# control.net
KiCad netlist of a schematic drawn in Altium Designer
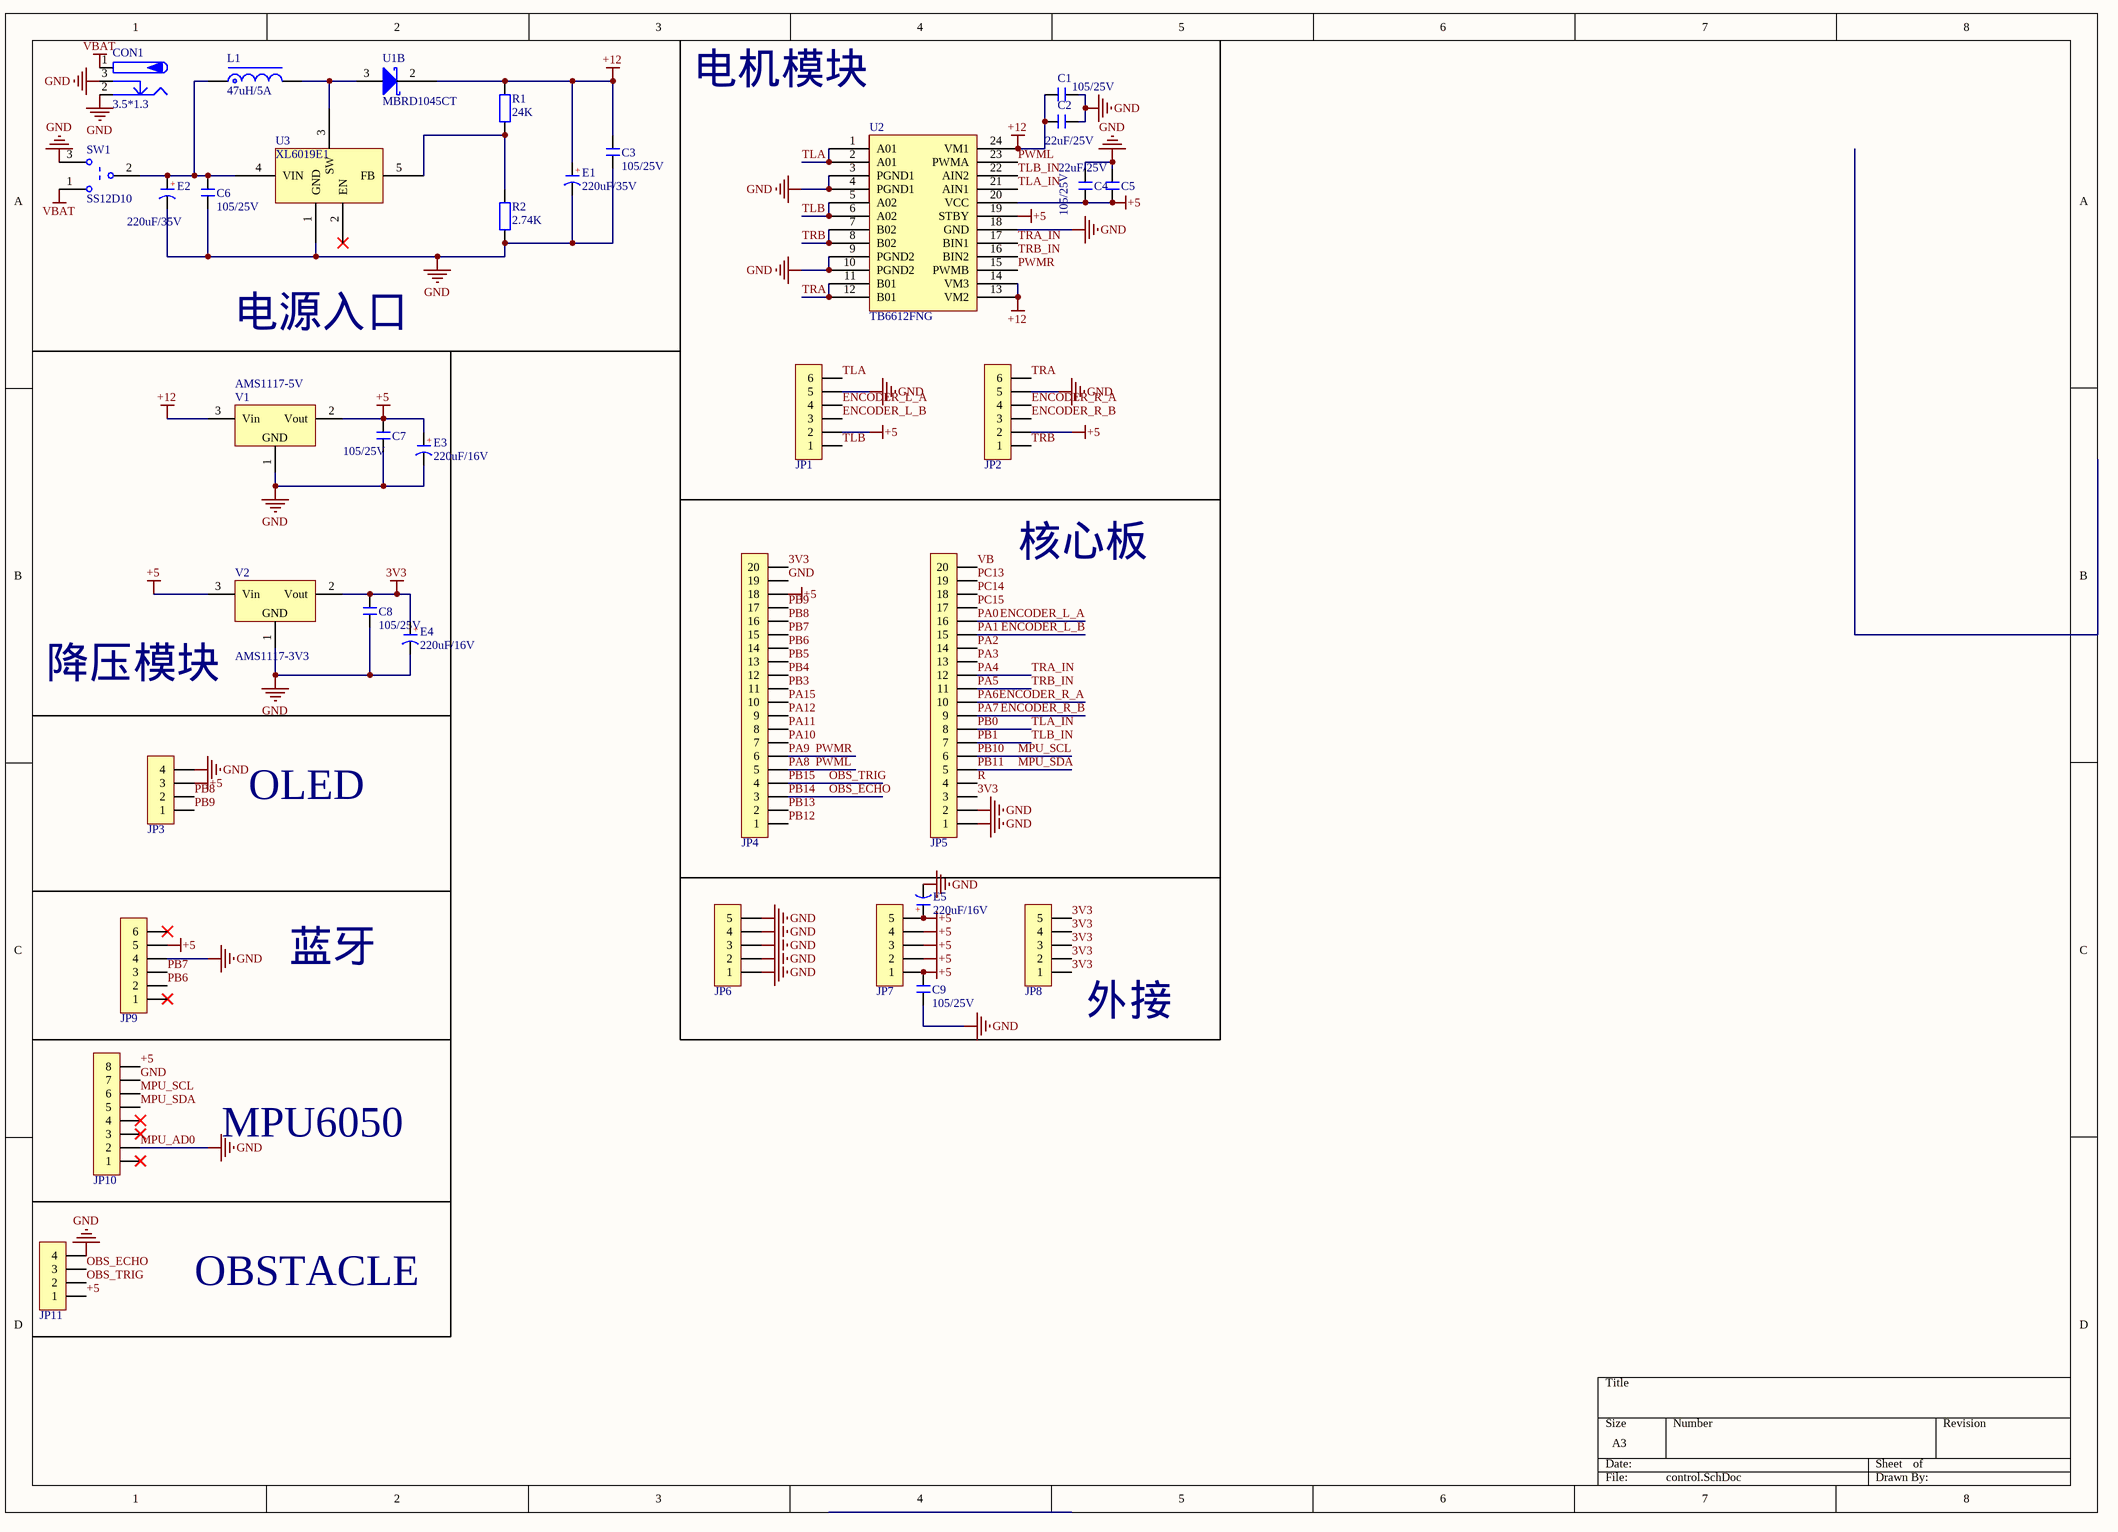
[diagram p0: control.SchDoc]

(export (version "E")
  (design (tool "Eeschema 10.0.6"))
  (components
    (comp (ref "C1")
      (value "105/25V")
      (footprint "C 0603_M")
      (description "贴片电容")
      (libsource (lib "0.1 - 电阻-电容-电感") (part "C"))
    )
    (comp (ref "C2")
      (value "22uF/25V")
      (footprint "C 0805_M")
      (description "贴片电容")
      (libsource (lib "0.1 - 电阻-电容-电感") (part "C"))
    )
    (comp (ref "C3")
      (value "105/25V")
      (footprint "C 0603_M")
      (description "贴片电容")
      (libsource (lib "0.1 - 电阻-电容-电感") (part "C"))
    )
    (comp (ref "C4")
      (value "105/25V")
      (footprint "C 0603_M")
      (description "贴片电容")
      (libsource (lib "0.1 - 电阻-电容-电感") (part "C"))
    )
    (comp (ref "C5")
      (value "22uF/25V")
      (footprint "C 0805_M")
      (description "贴片电容")
      (libsource (lib "0.1 - 电阻-电容-电感") (part "C"))
    )
    (comp (ref "C6")
      (value "105/25V")
      (footprint "C 0603_M")
      (description "贴片电容")
      (libsource (lib "0.1 - 电阻-电容-电感") (part "C"))
    )
    (comp (ref "C7")
      (value "105/25V")
      (footprint "C 0603_M")
      (description "贴片电容")
      (libsource (lib "0.1 - 电阻-电容-电感") (part "C"))
    )
    (comp (ref "C8")
      (value "105/25V")
      (footprint "C 0603_M")
      (description "贴片电容")
      (libsource (lib "0.1 - 电阻-电容-电感") (part "C"))
    )
    (comp (ref "C9")
      (value "105/25V")
      (footprint "C 0603_M")
      (description "贴片电容")
      (libsource (lib "0.1 - 电阻-电容-电感") (part "C"))
    )
    (comp (ref "CON1")
      (value "3.5*1.3")
      (footprint "DC-005")
      (description "低压电源接口")
      (fields (field (name "版权归属") "封装库来自淘宝 ID：黄晶宝石"))
      (libsource (lib "0.8 - 以太网-音频-USB插座") (part "P-DC"))
    )
    (comp (ref "E1")
      (value "220uF/35V")
      (footprint "CM E(8*10.2)")
      (description "贴片电解电容")
      (fields (field (name "版权归属") "封装库来自淘宝 ID：黄晶宝石"))
      (libsource (lib "0.1 - 电阻-电容-电感") (part "CE_SMD"))
    )
    (comp (ref "E2")
      (value "220uF/35V")
      (footprint "CM E(8*10.2)")
      (description "贴片电解电容")
      (fields (field (name "版权归属") "封装库来自淘宝 ID：黄晶宝石"))
      (libsource (lib "0.1 - 电阻-电容-电感") (part "CE_SMD"))
    )
    (comp (ref "E3")
      (value "220uF/16V")
      (footprint "CD D(7343)")
      (description "贴片钽电容")
      (libsource (lib "0.1 - 电阻-电容-电感") (part "CT"))
    )
    (comp (ref "E4")
      (value "220uF/16V")
      (footprint "CD D(7343)")
      (description "贴片钽电容")
      (libsource (lib "0.1 - 电阻-电容-电感") (part "CT"))
    )
    (comp (ref "E5")
      (value "220uF/16V")
      (footprint "CD D(7343)")
      (description "贴片钽电容")
      (libsource (lib "0.1 - 电阻-电容-电感") (part "CT"))
    )
    (comp (ref "JP1")
      (value "HDR-1X6")
      (footprint "XH2.54-LI-6P")
      (description "6P接插件")
      (fields (field (name "版权归属") "封装库来自淘宝 ID：黄晶宝石"))
      (libsource (lib "5.4 - 接插件-脚距2.54 (100mil) ") (part "Header 6"))
    )
    (comp (ref "JP2")
      (value "HDR-1X6")
      (footprint "XH2.54-LI-6P")
      (description "6P接插件")
      (fields (field (name "版权归属") "封装库来自淘宝 ID：黄晶宝石"))
      (libsource (lib "5.4 - 接插件-脚距2.54 (100mil) ") (part "Header 6"))
    )
    (comp (ref "JP3")
      (value "HDR-1X4")
      (footprint "HDR2.54-M-LI-4P")
      (description "4P接插件")
      (fields (field (name "版权归属") "封装库来自淘宝 ID：黄晶宝石"))
      (libsource (lib "5.4 - 接插件-脚距2.54 (100mil) ") (part "Header 4"))
    )
    (comp (ref "JP4")
      (value "HDR-1X20")
      (footprint "HDR2.54-M-LI-20P")
      (description "20P接插件")
      (fields (field (name "版权归属") "封装库来自淘宝 ID：黄晶宝石"))
      (libsource (lib "5.4 - 接插件-脚距2.54 (100mil) ") (part "Header 20"))
    )
    (comp (ref "JP5")
      (value "HDR-1X20")
      (footprint "HDR2.54-M-LI-20P")
      (description "20P接插件")
      (fields (field (name "版权归属") "封装库来自淘宝 ID：黄晶宝石"))
      (libsource (lib "5.4 - 接插件-脚距2.54 (100mil) ") (part "Header 20"))
    )
    (comp (ref "JP6")
      (value "HDR-1X5")
      (footprint "HDR2.54-LI-5P")
      (description "5P接插件")
      (fields (field (name "版权归属") "封装库来自淘宝 ID：黄晶宝石"))
      (libsource (lib "5.4 - 接插件-脚距2.54 (100mil) ") (part "Header 5"))
    )
    (comp (ref "JP7")
      (value "HDR-1X5")
      (footprint "HDR2.54-LI-5P")
      (description "5P接插件")
      (fields (field (name "版权归属") "封装库来自淘宝 ID：黄晶宝石"))
      (libsource (lib "5.4 - 接插件-脚距2.54 (100mil) ") (part "Header 5"))
    )
    (comp (ref "JP8")
      (value "HDR-1X5")
      (footprint "HDR2.54-LI-5P")
      (description "5P接插件")
      (fields (field (name "版权归属") "封装库来自淘宝 ID：黄晶宝石"))
      (libsource (lib "5.4 - 接插件-脚距2.54 (100mil) ") (part "Header 5"))
    )
    (comp (ref "JP9")
      (value "HDR-1X6")
      (footprint "HDR2.54-M-LI-6P")
      (description "6P接插件")
      (fields (field (name "版权归属") "封装库来自淘宝 ID：黄晶宝石"))
      (libsource (lib "5.4 - 接插件-脚距2.54 (100mil) ") (part "Header 6"))
    )
    (comp (ref "JP10")
      (value "HDR-1X8")
      (footprint "HDR2.54-M-LI-8P")
      (description "8P接插件")
      (fields (field (name "版权归属") "封装库来自淘宝 ID：黄晶宝石"))
      (libsource (lib "5.4 - 接插件-脚距2.54 (100mil) ") (part "Header 8"))
    )
    (comp (ref "JP11")
      (value "HDR-1X4")
      (footprint "HDR2.54-M-LI-4P")
      (description "4P接插件")
      (fields (field (name "版权归属") "封装库来自淘宝 ID：黄晶宝石"))
      (libsource (lib "5.4 - 接插件-脚距2.54 (100mil) ") (part "Header 4"))
    )
    (comp (ref "L1")
      (value "47uH/5A")
      (footprint "LMR135")
      (description "功率磁环电感")
      (libsource (lib "0.1 - 电阻-电容-电感") (part "L-MR"))
    )
    (comp (ref "R1")
      (value "24K")
      (footprint "R 0603_M")
      (description "贴片电阻")
      (fields (field (name "版权归属") "来自淘宝 ID：黄晶宝石"))
      (libsource (lib "0.1 - 电阻-电容-电感") (part "R"))
    )
    (comp (ref "R2")
      (value "2.74K")
      (footprint "R 0603_M")
      (description "贴片电阻")
      (fields (field (name "版权归属") "来自淘宝 ID：黄晶宝石"))
      (libsource (lib "0.1 - 电阻-电容-电感") (part "R"))
    )
    (comp (ref "SW1") (value "SS12D10") (footprint "SS12D10") (libsource (lib "LJY_LIB") (part "SS12D10")))
    (comp (ref "U1")
      (value "MBRD1045CT")
      (footprint "TO-252-3_L6.5-W5.5-P4.6-LS9.5-BL")
      (libsource (lib "LJY_LIB") (part "MBRD1045CT"))
    )
    (comp (ref "U2")
      (value "TB6612FNG")
      (footprint "TSOP65P760X160-24N")
      (libsource (lib "LJY_LIB") (part "TB6612FNG"))
    )
    (comp (ref "U3") (value "XL6019E1") (footprint "TO-263-5") (libsource (lib "LJY_LIB") (part "XL6019E1")))
    (comp (ref "V1")
      (value "AMS1117-5V")
      (footprint "SOT223_L")
      (description "三端稳压芯片")
      (libsource (lib "1.1 - 电源类芯片") (part "AMS1117"))
    )
    (comp (ref "V2")
      (value "AMS1117-3V3")
      (footprint "SOT223_L")
      (description "三端稳压芯片")
      (libsource (lib "1.1 - 电源类芯片") (part "AMS1117"))
    )
  )
  (nets
    (net (code "1") (name "+5") (class "Default")
      (node (ref "C4") (pin "2") (pinfunction "2_2") (pintype "passive"))
      (node (ref "C5") (pin "2") (pinfunction "2_2") (pintype "passive"))
      (node (ref "C7") (pin "2") (pinfunction "2_2") (pintype "passive"))
      (node (ref "C9") (pin "2") (pinfunction "2_2") (pintype "passive"))
      (node (ref "E3") (pin "1") (pinfunction "A_1") (pintype "passive"))
      (node (ref "E5") (pin "1") (pinfunction "A_1") (pintype "passive"))
      (node (ref "JP1") (pin "2") (pinfunction "2_2") (pintype "passive"))
      (node (ref "JP10") (pin "8") (pinfunction "8_8") (pintype "passive"))
      (node (ref "JP11") (pin "1") (pinfunction "1_1") (pintype "passive"))
      (node (ref "JP2") (pin "2") (pinfunction "2_2") (pintype "passive"))
      (node (ref "JP3") (pin "3") (pinfunction "3_3") (pintype "passive"))
      (node (ref "JP4") (pin "18") (pinfunction "18_18") (pintype "passive"))
      (node (ref "JP7") (pin "1") (pinfunction "1_1") (pintype "passive"))
      (node (ref "JP7") (pin "2") (pinfunction "2_2") (pintype "passive"))
      (node (ref "JP7") (pin "3") (pinfunction "3_3") (pintype "passive"))
      (node (ref "JP7") (pin "4") (pinfunction "4_4") (pintype "passive"))
      (node (ref "JP7") (pin "5") (pinfunction "5_5") (pintype "passive"))
      (node (ref "JP9") (pin "5") (pinfunction "5_5") (pintype "passive"))
      (node (ref "U2") (pin "19") (pinfunction "STBY_19") (pintype "passive"))
      (node (ref "U2") (pin "20") (pinfunction "VCC_20") (pintype "passive"))
      (node (ref "V1") (pin "2") (pinfunction "Vout_2") (pintype "passive"))
      (node (ref "V2") (pin "3") (pinfunction "Vin_3") (pintype "passive"))
    )
    (net (code "2") (name "+12") (class "Default")
      (node (ref "C1") (pin "2") (pinfunction "2_2") (pintype "passive"))
      (node (ref "C2") (pin "2") (pinfunction "2_2") (pintype "passive"))
      (node (ref "C3") (pin "2") (pinfunction "2_2") (pintype "passive"))
      (node (ref "E1") (pin "1") (pinfunction "A_1") (pintype "passive"))
      (node (ref "R1") (pin "2") (pinfunction "2_2") (pintype "passive"))
      (node (ref "U1") (pin "2") (pinfunction "3_2") (pintype "passive"))
      (node (ref "U2") (pin "13") (pinfunction "VM2_13") (pintype "passive"))
      (node (ref "U2") (pin "14") (pinfunction "VM3_14") (pintype "passive"))
      (node (ref "U2") (pin "24") (pinfunction "VM1_24") (pintype "passive"))
      (node (ref "V1") (pin "3") (pinfunction "Vin_3") (pintype "passive"))
    )
    (net (code "3") (name "/ENCODER_L_A") (class "Default")
      (node (ref "JP1") (pin "4") (pinfunction "4_4") (pintype "passive"))
      (node (ref "JP5") (pin "16") (pinfunction "16_16") (pintype "passive"))
    )
    (net (code "4") (name "/ENCODER_L_B") (class "Default")
      (node (ref "JP1") (pin "3") (pinfunction "3_3") (pintype "passive"))
      (node (ref "JP5") (pin "15") (pinfunction "15_15") (pintype "passive"))
    )
    (net (code "5") (name "/ENCODER_R_A") (class "Default")
      (node (ref "JP2") (pin "4") (pinfunction "4_4") (pintype "passive"))
      (node (ref "JP5") (pin "10") (pinfunction "10_10") (pintype "passive"))
    )
    (net (code "6") (name "/ENCODER_R_B") (class "Default")
      (node (ref "JP2") (pin "3") (pinfunction "3_3") (pintype "passive"))
      (node (ref "JP5") (pin "9") (pinfunction "9_9") (pintype "passive"))
    )
    (net (code "7") (name "/MPU_SCL") (class "Default")
      (node (ref "JP10") (pin "6") (pinfunction "6_6") (pintype "passive"))
      (node (ref "JP5") (pin "6") (pinfunction "6_6") (pintype "passive"))
    )
    (net (code "8") (name "/MPU_SDA") (class "Default")
      (node (ref "JP10") (pin "5") (pinfunction "5_5") (pintype "passive"))
      (node (ref "JP5") (pin "5") (pinfunction "5_5") (pintype "passive"))
    )
    (net (code "9") (name "/OBS_ECHO") (class "Default")
      (node (ref "JP11") (pin "3") (pinfunction "3_3") (pintype "passive"))
      (node (ref "JP4") (pin "3") (pinfunction "3_3") (pintype "passive"))
    )
    (net (code "10") (name "/OBS_TRIG") (class "Default")
      (node (ref "JP11") (pin "2") (pinfunction "2_2") (pintype "passive"))
      (node (ref "JP4") (pin "4") (pinfunction "4_4") (pintype "passive"))
    )
    (net (code "11") (name "/PA2") (class "Default")
      (node (ref "JP5") (pin "14") (pinfunction "14_14") (pintype "passive"))
    )
    (net (code "12") (name "/PA3") (class "Default")
      (node (ref "JP5") (pin "13") (pinfunction "13_13") (pintype "passive"))
    )
    (net (code "13") (name "/PA4") (class "Default")
      (node (ref "JP5") (pin "12") (pinfunction "12_12") (pintype "passive"))
      (node (ref "U2") (pin "17") (pinfunction "BIN1_17") (pintype "passive"))
    )
    (net (code "14") (name "/PA5") (class "Default")
      (node (ref "JP5") (pin "11") (pinfunction "11_11") (pintype "passive"))
      (node (ref "U2") (pin "16") (pinfunction "BIN2_16") (pintype "passive"))
    )
    (net (code "15") (name "/PA8") (class "Default")
      (node (ref "JP4") (pin "5") (pinfunction "5_5") (pintype "passive"))
      (node (ref "U2") (pin "23") (pinfunction "PWMA_23") (pintype "passive"))
    )
    (net (code "16") (name "/PA9") (class "Default")
      (node (ref "JP4") (pin "6") (pinfunction "6_6") (pintype "passive"))
      (node (ref "U2") (pin "15") (pinfunction "PWMB_15") (pintype "passive"))
    )
    (net (code "17") (name "/PA10") (class "Default")
      (node (ref "JP4") (pin "7") (pinfunction "7_7") (pintype "passive"))
    )
    (net (code "18") (name "/PA11") (class "Default")
      (node (ref "JP4") (pin "8") (pinfunction "8_8") (pintype "passive"))
    )
    (net (code "19") (name "/PA12") (class "Default")
      (node (ref "JP4") (pin "9") (pinfunction "9_9") (pintype "passive"))
    )
    (net (code "20") (name "/PA15") (class "Default")
      (node (ref "JP4") (pin "10") (pinfunction "10_10") (pintype "passive"))
    )
    (net (code "21") (name "/PB0") (class "Default")
      (node (ref "JP5") (pin "8") (pinfunction "8_8") (pintype "passive"))
      (node (ref "U2") (pin "21") (pinfunction "AIN1_21") (pintype "passive"))
    )
    (net (code "22") (name "/PB1") (class "Default")
      (node (ref "JP5") (pin "7") (pinfunction "7_7") (pintype "passive"))
      (node (ref "U2") (pin "22") (pinfunction "AIN2_22") (pintype "passive"))
    )
    (net (code "23") (name "/PB3") (class "Default")
      (node (ref "JP4") (pin "11") (pinfunction "11_11") (pintype "passive"))
    )
    (net (code "24") (name "/PB4") (class "Default")
      (node (ref "JP4") (pin "12") (pinfunction "12_12") (pintype "passive"))
    )
    (net (code "25") (name "/PB5") (class "Default")
      (node (ref "JP4") (pin "13") (pinfunction "13_13") (pintype "passive"))
    )
    (net (code "26") (name "/PB6") (class "Default")
      (node (ref "JP4") (pin "14") (pinfunction "14_14") (pintype "passive"))
      (node (ref "JP9") (pin "2") (pinfunction "2_2") (pintype "passive"))
    )
    (net (code "27") (name "/PB7") (class "Default")
      (node (ref "JP4") (pin "15") (pinfunction "15_15") (pintype "passive"))
      (node (ref "JP9") (pin "3") (pinfunction "3_3") (pintype "passive"))
    )
    (net (code "28") (name "/PB8") (class "Default")
      (node (ref "JP3") (pin "2") (pinfunction "2_2") (pintype "passive"))
      (node (ref "JP4") (pin "16") (pinfunction "16_16") (pintype "passive"))
    )
    (net (code "29") (name "/PB9") (class "Default")
      (node (ref "JP3") (pin "1") (pinfunction "1_1") (pintype "passive"))
      (node (ref "JP4") (pin "17") (pinfunction "17_17") (pintype "passive"))
    )
    (net (code "30") (name "/PB12") (class "Default")
      (node (ref "JP4") (pin "1") (pinfunction "1_1") (pintype "passive"))
    )
    (net (code "31") (name "/PB13") (class "Default")
      (node (ref "JP4") (pin "2") (pinfunction "2_2") (pintype "passive"))
    )
    (net (code "32") (name "/PC13") (class "Default")
      (node (ref "JP5") (pin "19") (pinfunction "19_19") (pintype "passive"))
    )
    (net (code "33") (name "/PC14") (class "Default")
      (node (ref "JP5") (pin "18") (pinfunction "18_18") (pintype "passive"))
    )
    (net (code "34") (name "/PC15") (class "Default")
      (node (ref "JP5") (pin "17") (pinfunction "17_17") (pintype "passive"))
    )
    (net (code "35") (name "/R") (class "Default")
      (node (ref "JP5") (pin "4") (pinfunction "4_4") (pintype "passive"))
    )
    (net (code "36") (name "/TLA") (class "Default")
      (node (ref "JP1") (pin "6") (pinfunction "6_6") (pintype "passive"))
      (node (ref "U2") (pin "1") (pinfunction "A01_1") (pintype "passive"))
      (node (ref "U2") (pin "2") (pinfunction "A01_2") (pintype "passive"))
    )
    (net (code "37") (name "/TLB") (class "Default")
      (node (ref "JP1") (pin "1") (pinfunction "1_1") (pintype "passive"))
      (node (ref "U2") (pin "5") (pinfunction "A02_5") (pintype "passive"))
      (node (ref "U2") (pin "6") (pinfunction "A02_6") (pintype "passive"))
    )
    (net (code "38") (name "/TRA") (class "Default")
      (node (ref "JP2") (pin "6") (pinfunction "6_6") (pintype "passive"))
      (node (ref "U2") (pin "11") (pinfunction "B01_11") (pintype "passive"))
      (node (ref "U2") (pin "12") (pinfunction "B01_12") (pintype "passive"))
    )
    (net (code "39") (name "/TRB") (class "Default")
      (node (ref "JP2") (pin "1") (pinfunction "1_1") (pintype "passive"))
      (node (ref "U2") (pin "7") (pinfunction "B02_7") (pintype "passive"))
      (node (ref "U2") (pin "8") (pinfunction "B02_8") (pintype "passive"))
    )
    (net (code "40") (name "/VB") (class "Default")
      (node (ref "JP5") (pin "20") (pinfunction "20_20") (pintype "passive"))
    )
    (net (code "41") (name "3V3") (class "Default")
      (node (ref "C8") (pin "2") (pinfunction "2_2") (pintype "passive"))
      (node (ref "E4") (pin "1") (pinfunction "A_1") (pintype "passive"))
      (node (ref "JP4") (pin "20") (pinfunction "20_20") (pintype "passive"))
      (node (ref "JP5") (pin "3") (pinfunction "3_3") (pintype "passive"))
      (node (ref "JP8") (pin "1") (pinfunction "1_1") (pintype "passive"))
      (node (ref "JP8") (pin "2") (pinfunction "2_2") (pintype "passive"))
      (node (ref "JP8") (pin "3") (pinfunction "3_3") (pintype "passive"))
      (node (ref "JP8") (pin "4") (pinfunction "4_4") (pintype "passive"))
      (node (ref "JP8") (pin "5") (pinfunction "5_5") (pintype "passive"))
      (node (ref "V2") (pin "2") (pinfunction "Vout_2") (pintype "passive"))
    )
    (net (code "42") (name "GND") (class "Default")
      (node (ref "C1") (pin "1") (pinfunction "1_1") (pintype "passive"))
      (node (ref "C2") (pin "1") (pinfunction "1_1") (pintype "passive"))
      (node (ref "C3") (pin "1") (pinfunction "1_1") (pintype "passive"))
      (node (ref "C4") (pin "1") (pinfunction "1_1") (pintype "passive"))
      (node (ref "C5") (pin "1") (pinfunction "1_1") (pintype "passive"))
      (node (ref "C6") (pin "1") (pinfunction "1_1") (pintype "passive"))
      (node (ref "C7") (pin "1") (pinfunction "1_1") (pintype "passive"))
      (node (ref "C8") (pin "1") (pinfunction "1_1") (pintype "passive"))
      (node (ref "C9") (pin "1") (pinfunction "1_1") (pintype "passive"))
      (node (ref "CON1") (pin "2") (pintype "power_in"))
      (node (ref "CON1") (pin "3") (pintype "power_in"))
      (node (ref "E1") (pin "2") (pinfunction "K_2") (pintype "passive"))
      (node (ref "E2") (pin "2") (pinfunction "K_2") (pintype "passive"))
      (node (ref "E3") (pin "2") (pinfunction "K_2") (pintype "passive"))
      (node (ref "E4") (pin "2") (pinfunction "K_2") (pintype "passive"))
      (node (ref "E5") (pin "2") (pinfunction "K_2") (pintype "passive"))
      (node (ref "JP1") (pin "5") (pinfunction "5_5") (pintype "passive"))
      (node (ref "JP10") (pin "2") (pinfunction "2_2") (pintype "passive"))
      (node (ref "JP10") (pin "7") (pinfunction "7_7") (pintype "passive"))
      (node (ref "JP11") (pin "4") (pinfunction "4_4") (pintype "passive"))
      (node (ref "JP2") (pin "5") (pinfunction "5_5") (pintype "passive"))
      (node (ref "JP3") (pin "4") (pinfunction "4_4") (pintype "passive"))
      (node (ref "JP4") (pin "19") (pinfunction "19_19") (pintype "passive"))
      (node (ref "JP5") (pin "1") (pinfunction "1_1") (pintype "passive"))
      (node (ref "JP5") (pin "2") (pinfunction "2_2") (pintype "passive"))
      (node (ref "JP6") (pin "1") (pinfunction "1_1") (pintype "passive"))
      (node (ref "JP6") (pin "2") (pinfunction "2_2") (pintype "passive"))
      (node (ref "JP6") (pin "3") (pinfunction "3_3") (pintype "passive"))
      (node (ref "JP6") (pin "4") (pinfunction "4_4") (pintype "passive"))
      (node (ref "JP6") (pin "5") (pinfunction "5_5") (pintype "passive"))
      (node (ref "JP9") (pin "4") (pinfunction "4_4") (pintype "passive"))
      (node (ref "R2") (pin "2") (pinfunction "2_2") (pintype "passive"))
      (node (ref "SW1") (pin "3") (pinfunction "NO1_3") (pintype "passive"))
      (node (ref "U2") (pin "10") (pinfunction "PGND2_10") (pintype "passive"))
      (node (ref "U2") (pin "18") (pinfunction "GND_18") (pintype "passive"))
      (node (ref "U2") (pin "3") (pinfunction "PGND1_3") (pintype "passive"))
      (node (ref "U2") (pin "4") (pinfunction "PGND1_4") (pintype "passive"))
      (node (ref "U2") (pin "9") (pinfunction "PGND2_9") (pintype "passive"))
      (node (ref "U3") (pin "1") (pinfunction "GND_1") (pintype "passive"))
      (node (ref "V1") (pin "1") (pinfunction "GND_1") (pintype "passive"))
      (node (ref "V2") (pin "1") (pinfunction "GND_1") (pintype "passive"))
    )
    (net (code "43") (name "Net-(E2-A)") (class "Default")
      (node (ref "C6") (pin "2") (pinfunction "2_2") (pintype "passive"))
      (node (ref "E2") (pin "1") (pinfunction "A_1") (pintype "passive"))
      (node (ref "L1") (pin "1") (pinfunction "1_1") (pintype "passive"))
      (node (ref "SW1") (pin "2") (pinfunction "COM2_2") (pintype "passive"))
      (node (ref "U3") (pin "4") (pinfunction "VIN_4") (pintype "passive"))
    )
    (net (code "44") (name "Net-(U1B-A)") (class "Default")
      (node (ref "L1") (pin "2") (pinfunction "2_2") (pintype "passive"))
      (node (ref "U1") (pin "3") (pinfunction "A_3") (pintype "passive"))
      (node (ref "U3") (pin "3") (pinfunction "SW_3") (pintype "passive"))
    )
    (net (code "45") (name "Net-(U3-FB)") (class "Default")
      (node (ref "R1") (pin "1") (pinfunction "1_1") (pintype "passive"))
      (node (ref "R2") (pin "1") (pinfunction "1_1") (pintype "passive"))
      (node (ref "U3") (pin "5") (pinfunction "FB_5") (pintype "passive"))
    )
    (net (code "46") (name "VBAT") (class "Default")
      (node (ref "CON1") (pin "1") (pintype "power_in"))
      (node (ref "SW1") (pin "1") (pinfunction "NC1_1") (pintype "passive"))
    )
    (net (code "47") (name "unconnected-(JP9-Pad1)") (class "Default")
      (node (ref "JP9") (pin "1") (pinfunction "1_1") (pintype "passive+no_connect"))
    )
    (net (code "48") (name "unconnected-(JP9-Pad6)") (class "Default")
      (node (ref "JP9") (pin "6") (pinfunction "6_6") (pintype "passive+no_connect"))
    )
    (net (code "49") (name "unconnected-(JP10-Pad1)") (class "Default")
      (node (ref "JP10") (pin "1") (pinfunction "1_1") (pintype "passive+no_connect"))
    )
    (net (code "50") (name "unconnected-(JP10-Pad3)") (class "Default")
      (node (ref "JP10") (pin "3") (pinfunction "3_3") (pintype "passive+no_connect"))
    )
    (net (code "51") (name "unconnected-(JP10-Pad4)") (class "Default")
      (node (ref "JP10") (pin "4") (pinfunction "4_4") (pintype "passive+no_connect"))
    )
    (net (code "52") (name "unconnected-(U3-EN-Pad2)") (class "Default")
      (node (ref "U3") (pin "2") (pinfunction "EN_2") (pintype "passive+no_connect"))
    )
  )
)
